# WIFI.net
KiCad netlist of a schematic drawn in Altium Designer
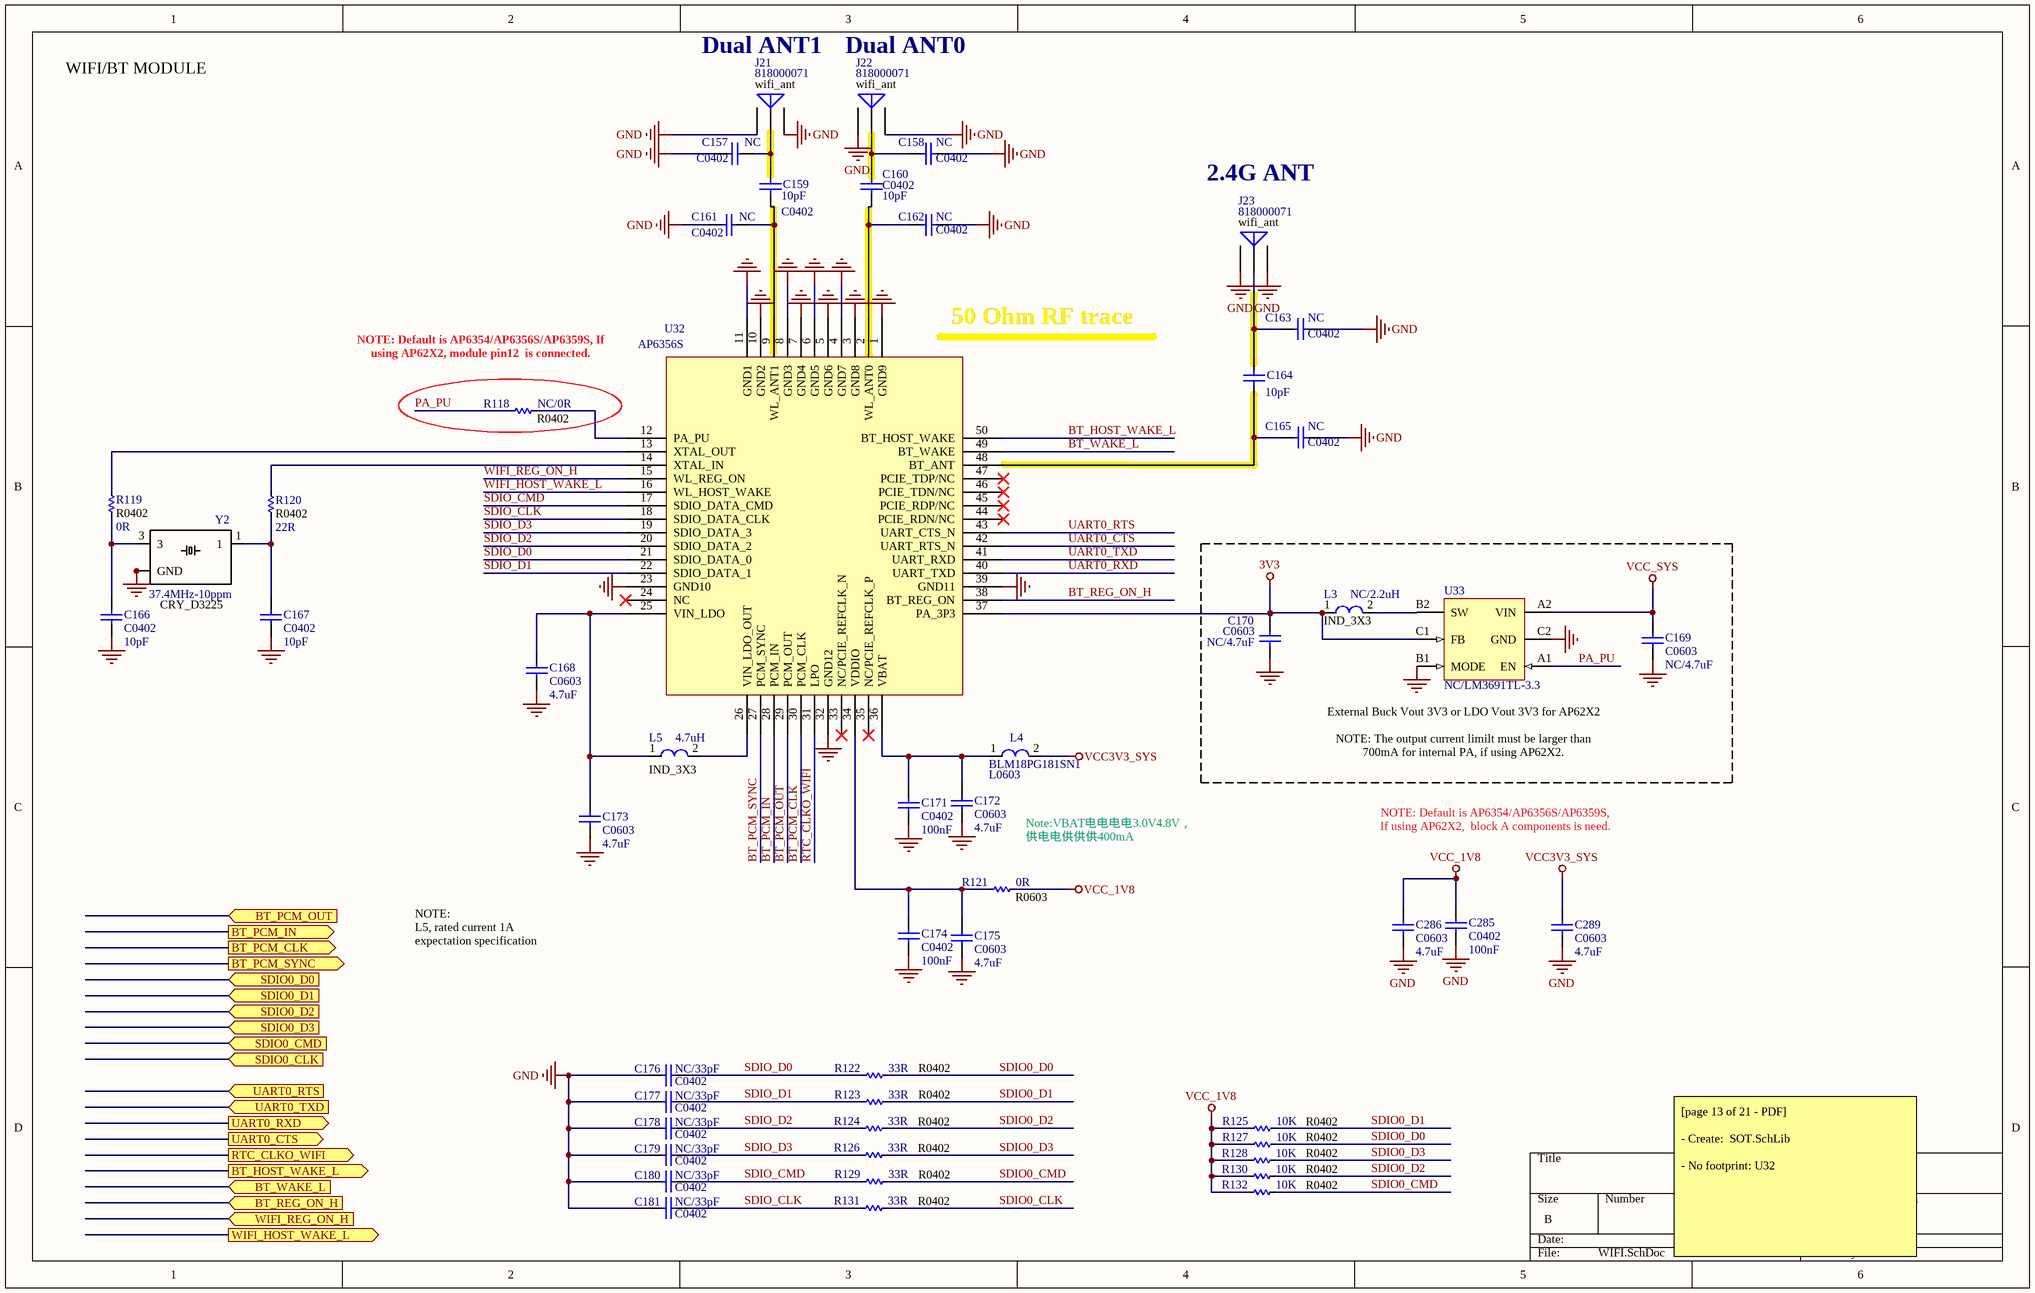
[diagram p0: WIFI.SchDoc]

(export (version "E")
  (design (tool "Eeschema 10.0.6"))
  (components
    (comp (ref "C157")
      (value "C0402")
      (footprint "C 0402")
      (description "Capacitor")
      (fields (field (name "ALTIUM_VALUE") "NC") (field (name "PUBLISHER") "Altium Limited"))
      (libsource (lib "Miscellaneous Devices") (part "Cap"))
    )
    (comp (ref "C158")
      (value "C0402")
      (footprint "C 0402")
      (description "Capacitor")
      (fields (field (name "ALTIUM_VALUE") "NC") (field (name "PUBLISHER") "Altium Limited"))
      (libsource (lib "Miscellaneous Devices") (part "Cap"))
    )
    (comp (ref "C159")
      (value "C0402")
      (footprint "C 0402")
      (description "Capacitor")
      (fields (field (name "ALTIUM_VALUE") "10pF") (field (name "PUBLISHER") "Altium Limited"))
      (libsource (lib "Miscellaneous Devices") (part "Cap"))
    )
    (comp (ref "C160")
      (value "C0402")
      (footprint "C 0402")
      (description "Capacitor")
      (fields (field (name "ALTIUM_VALUE") "10pF") (field (name "PUBLISHER") "Altium Limited"))
      (libsource (lib "Miscellaneous Devices") (part "Cap"))
    )
    (comp (ref "C161")
      (value "C0402")
      (footprint "C 0402")
      (description "Capacitor")
      (fields (field (name "ALTIUM_VALUE") "NC") (field (name "PUBLISHER") "Altium Limited"))
      (libsource (lib "Miscellaneous Devices") (part "Cap"))
    )
    (comp (ref "C162")
      (value "C0402")
      (footprint "C 0402")
      (description "Capacitor")
      (fields (field (name "ALTIUM_VALUE") "NC") (field (name "PUBLISHER") "Altium Limited"))
      (libsource (lib "Miscellaneous Devices") (part "Cap"))
    )
    (comp (ref "C163")
      (value "C0402")
      (footprint "C 0402")
      (description "Capacitor")
      (fields (field (name "ALTIUM_VALUE") "NC") (field (name "PUBLISHER") "Altium Limited"))
      (libsource (lib "Miscellaneous Devices") (part "Cap"))
    )
    (comp (ref "C164")
      (value "10pF")
      (footprint "C 0402")
      (description "Capacitor")
      (fields (field (name "Comment") "C0402") (field (name "PUBLISHER") "Altium Limited"))
      (libsource (lib "Miscellaneous Devices") (part "Cap"))
    )
    (comp (ref "C165")
      (value "C0402")
      (footprint "C 0402")
      (description "Capacitor")
      (fields (field (name "ALTIUM_VALUE") "NC") (field (name "PUBLISHER") "Altium Limited"))
      (libsource (lib "Miscellaneous Devices") (part "Cap"))
    )
    (comp (ref "C166")
      (value "C0402")
      (footprint "C 0402")
      (description "Capacitor")
      (fields (field (name "ALTIUM_VALUE") "10pF") (field (name "PUBLISHER") "Altium Limited"))
      (libsource (lib "Miscellaneous Devices") (part "Cap"))
    )
    (comp (ref "C167")
      (value "C0402")
      (footprint "C 0402")
      (description "Capacitor")
      (fields (field (name "ALTIUM_VALUE") "10pF") (field (name "PUBLISHER") "Altium Limited"))
      (libsource (lib "Miscellaneous Devices") (part "Cap"))
    )
    (comp (ref "C168")
      (value "C0603")
      (footprint "C 0603")
      (description "Capacitor")
      (fields (field (name "ALTIUM_VALUE") "4.7uF") (field (name "PUBLISHER") "Altium Limited"))
      (libsource (lib "Miscellaneous Devices") (part "Cap"))
    )
    (comp (ref "C169")
      (value "C0603")
      (footprint "C 0603")
      (description "Capacitor")
      (fields (field (name "ALTIUM_VALUE") "NC/4.7uF") (field (name "PUBLISHER") "Altium Limited"))
      (libsource (lib "Miscellaneous Devices") (part "Cap"))
    )
    (comp (ref "C170")
      (value "C0603")
      (footprint "C 0603")
      (description "Capacitor")
      (fields (field (name "ALTIUM_VALUE") "NC/4.7uF") (field (name "PUBLISHER") "Altium Limited"))
      (libsource (lib "Miscellaneous Devices") (part "Cap"))
    )
    (comp (ref "C171")
      (value "C0402")
      (footprint "C 0402")
      (description "Capacitor")
      (fields (field (name "ALTIUM_VALUE") "100nF") (field (name "PUBLISHER") "Altium Limited"))
      (libsource (lib "Miscellaneous Devices") (part "Cap"))
    )
    (comp (ref "C172")
      (value "C0603")
      (footprint "C 0603")
      (description "Capacitor")
      (fields (field (name "ALTIUM_VALUE") "4.7uF") (field (name "PUBLISHER") "Altium Limited"))
      (libsource (lib "Miscellaneous Devices") (part "Cap"))
    )
    (comp (ref "C173")
      (value "C0603")
      (footprint "C 0603")
      (description "Capacitor")
      (fields (field (name "ALTIUM_VALUE") "4.7uF") (field (name "PUBLISHER") "Altium Limited"))
      (libsource (lib "Miscellaneous Devices") (part "Cap"))
    )
    (comp (ref "C174")
      (value "C0402")
      (footprint "C 0402")
      (description "Capacitor")
      (fields (field (name "ALTIUM_VALUE") "100nF") (field (name "PUBLISHER") "Altium Limited"))
      (libsource (lib "Miscellaneous Devices") (part "Cap"))
    )
    (comp (ref "C175")
      (value "C0603")
      (footprint "C 0603")
      (description "Capacitor")
      (fields (field (name "ALTIUM_VALUE") "4.7uF") (field (name "PUBLISHER") "Altium Limited"))
      (libsource (lib "Miscellaneous Devices") (part "Cap"))
    )
    (comp (ref "C176")
      (value "C0402")
      (footprint "C 0402")
      (description "Capacitor")
      (fields (field (name "ALTIUM_VALUE") "NC/33pF") (field (name "PUBLISHER") "Altium Limited"))
      (libsource (lib "Miscellaneous Devices") (part "Cap"))
    )
    (comp (ref "C177")
      (value "C0402")
      (footprint "C 0402")
      (description "Capacitor")
      (fields (field (name "ALTIUM_VALUE") "NC/33pF") (field (name "PUBLISHER") "Altium Limited"))
      (libsource (lib "Miscellaneous Devices") (part "Cap"))
    )
    (comp (ref "C178")
      (value "C0402")
      (footprint "C 0402")
      (description "Capacitor")
      (fields (field (name "ALTIUM_VALUE") "NC/33pF") (field (name "PUBLISHER") "Altium Limited"))
      (libsource (lib "Miscellaneous Devices") (part "Cap"))
    )
    (comp (ref "C179")
      (value "C0402")
      (footprint "C 0402")
      (description "Capacitor")
      (fields (field (name "ALTIUM_VALUE") "NC/33pF") (field (name "PUBLISHER") "Altium Limited"))
      (libsource (lib "Miscellaneous Devices") (part "Cap"))
    )
    (comp (ref "C180")
      (value "C0402")
      (footprint "C 0402")
      (description "Capacitor")
      (fields (field (name "ALTIUM_VALUE") "NC/33pF") (field (name "PUBLISHER") "Altium Limited"))
      (libsource (lib "Miscellaneous Devices") (part "Cap"))
    )
    (comp (ref "C181")
      (value "C0402")
      (footprint "C 0402")
      (description "Capacitor")
      (fields (field (name "ALTIUM_VALUE") "NC/33pF") (field (name "PUBLISHER") "Altium Limited"))
      (libsource (lib "Miscellaneous Devices") (part "Cap"))
    )
    (comp (ref "C285")
      (value "C0402")
      (footprint "C 0402")
      (description "Capacitor")
      (fields (field (name "ALTIUM_VALUE") "100nF") (field (name "PUBLISHER") "Altium Limited"))
      (libsource (lib "Miscellaneous Devices") (part "Cap"))
    )
    (comp (ref "C286")
      (value "C0603")
      (footprint "C 0603")
      (description "Capacitor")
      (fields (field (name "ALTIUM_VALUE") "4.7uF") (field (name "PUBLISHER") "Altium Limited"))
      (libsource (lib "Miscellaneous Devices") (part "Cap"))
    )
    (comp (ref "C289")
      (value "C0603")
      (footprint "C 0603")
      (description "Capacitor")
      (fields (field (name "ALTIUM_VALUE") "4.7uF") (field (name "PUBLISHER") "Altium Limited"))
      (libsource (lib "Miscellaneous Devices") (part "Cap"))
    )
    (comp (ref "J21")
      (value "818000071")
      (footprint "CONN/IPX/SMD")
      (description "Generic Antenna")
      (fields (field (name "ALTIUM_UNNAMED_1") "wifi_ant") (field (name "PUBLISHER") "Altium Limited"))
      (libsource (lib "SOT") (part "Antenna"))
    )
    (comp (ref "J22")
      (value "818000071")
      (footprint "CONN/IPX/SMD")
      (description "Generic Antenna")
      (fields (field (name "ALTIUM_UNNAMED_1") "wifi_ant") (field (name "PUBLISHER") "Altium Limited"))
      (libsource (lib "SOT") (part "Antenna"))
    )
    (comp (ref "J23")
      (value "818000071")
      (footprint "CONN/IPX/SMD")
      (description "Generic Antenna")
      (fields (field (name "ALTIUM_UNNAMED_1") "wifi_ant") (field (name "PUBLISHER") "Altium Limited"))
      (libsource (lib "SOT") (part "Antenna"))
    )
    (comp (ref "L3")
      (value "NC/2.2uH")
      (footprint "L-SMD-M-7.3x4.5")
      (fields
        (field (name "PARTNO") "78477010")
        (field (name "MANUFACTURER") "Wurth Elektronik")
        (field (name "ALTIUM_UNNAMED_1") "IND_3X3")
        (field (name "CREATED BY") "Baojun Chen")
      )
      (libsource (lib "LIBRARY") (part "L-SMD-1"))
    )
    (comp (ref "L4")
      (value "L0603")
      (footprint "L-SMD-M-12x10")
      (fields
        (field (name "PARTNO") "78477010")
        (field (name "MANUFACTURER") "Wurth Elektronik")
        (field (name "ALTIUM_UNNAMED_1") "BLM18PG181SN1")
        (field (name "CREATED BY") "Baojun Chen")
      )
      (libsource (lib "LIBRARY") (part "L-SMD-1"))
    )
    (comp (ref "L5")
      (value "4.7uH")
      (footprint "L-SMD-M-7.3x4.5")
      (fields
        (field (name "PARTNO") "78477010")
        (field (name "MANUFACTURER") "Wurth Elektronik")
        (field (name "ALTIUM_UNNAMED_1") "IND_3X3")
        (field (name "CREATED BY") "Baojun Chen")
      )
      (libsource (lib "LIBRARY") (part "L-SMD-1"))
    )
    (comp (ref "R118")
      (value "R0402")
      (footprint "R 0402")
      (description "Resistor")
      (fields
        (field (name "MANUFACTURER") "Generic Components")
        (field (name "ALTIUM_VALUE") "NC/0R")
        (field (name "PUBLISHER") "Altium Hobart Technology Centre")
      )
      (libsource (lib "LIBRARY") (part "Res-SMD"))
    )
    (comp (ref "R119")
      (value "R0402")
      (footprint "R 0402")
      (description "Resistor")
      (fields
        (field (name "MANUFACTURER") "Generic Components")
        (field (name "ALTIUM_VALUE") "0R")
        (field (name "PUBLISHER") "Altium Hobart Technology Centre")
      )
      (libsource (lib "LIBRARY") (part "Res-SMD"))
    )
    (comp (ref "R120")
      (value "R0402")
      (footprint "R 0402")
      (description "Resistor")
      (fields
        (field (name "MANUFACTURER") "Generic Components")
        (field (name "ALTIUM_VALUE") "22R")
        (field (name "PUBLISHER") "Altium Hobart Technology Centre")
      )
      (libsource (lib "LIBRARY") (part "Res-SMD"))
    )
    (comp (ref "R121")
      (value "R0603")
      (footprint "R 0603")
      (description "Resistor")
      (fields
        (field (name "MANUFACTURER") "Generic Components")
        (field (name "ALTIUM_VALUE") "0R")
        (field (name "PUBLISHER") "Altium Hobart Technology Centre")
      )
      (libsource (lib "LIBRARY") (part "Res-SMD"))
    )
    (comp (ref "R122")
      (value "R0402")
      (footprint "R 0402")
      (description "Resistor")
      (fields
        (field (name "MANUFACTURER") "Generic Components")
        (field (name "ALTIUM_VALUE") "33R")
        (field (name "PUBLISHER") "Altium Hobart Technology Centre")
      )
      (libsource (lib "LIBRARY") (part "Res-SMD"))
    )
    (comp (ref "R123")
      (value "R0402")
      (footprint "R 0402")
      (description "Resistor")
      (fields
        (field (name "MANUFACTURER") "Generic Components")
        (field (name "ALTIUM_VALUE") "33R")
        (field (name "PUBLISHER") "Altium Hobart Technology Centre")
      )
      (libsource (lib "LIBRARY") (part "Res-SMD"))
    )
    (comp (ref "R124")
      (value "R0402")
      (footprint "R 0402")
      (description "Resistor")
      (fields
        (field (name "MANUFACTURER") "Generic Components")
        (field (name "ALTIUM_VALUE") "33R")
        (field (name "PUBLISHER") "Altium Hobart Technology Centre")
      )
      (libsource (lib "LIBRARY") (part "Res-SMD"))
    )
    (comp (ref "R125")
      (value "R0402")
      (footprint "R 0402")
      (description "Resistor")
      (fields
        (field (name "MANUFACTURER") "Generic Components")
        (field (name "ALTIUM_VALUE") "10K")
        (field (name "PUBLISHER") "Altium Hobart Technology Centre")
      )
      (libsource (lib "LIBRARY") (part "Res-SMD"))
    )
    (comp (ref "R126")
      (value "R0402")
      (footprint "R 0402")
      (description "Resistor")
      (fields
        (field (name "MANUFACTURER") "Generic Components")
        (field (name "ALTIUM_VALUE") "33R")
        (field (name "PUBLISHER") "Altium Hobart Technology Centre")
      )
      (libsource (lib "LIBRARY") (part "Res-SMD"))
    )
    (comp (ref "R127")
      (value "R0402")
      (footprint "R 0402")
      (description "Resistor")
      (fields
        (field (name "MANUFACTURER") "Generic Components")
        (field (name "ALTIUM_VALUE") "10K")
        (field (name "PUBLISHER") "Altium Hobart Technology Centre")
      )
      (libsource (lib "LIBRARY") (part "Res-SMD"))
    )
    (comp (ref "R128")
      (value "R0402")
      (footprint "R 0402")
      (description "Resistor")
      (fields
        (field (name "MANUFACTURER") "Generic Components")
        (field (name "ALTIUM_VALUE") "10K")
        (field (name "PUBLISHER") "Altium Hobart Technology Centre")
      )
      (libsource (lib "LIBRARY") (part "Res-SMD"))
    )
    (comp (ref "R129")
      (value "R0402")
      (footprint "R 0402")
      (description "Resistor")
      (fields
        (field (name "MANUFACTURER") "Generic Components")
        (field (name "ALTIUM_VALUE") "33R")
        (field (name "PUBLISHER") "Altium Hobart Technology Centre")
      )
      (libsource (lib "LIBRARY") (part "Res-SMD"))
    )
    (comp (ref "R130")
      (value "R0402")
      (footprint "R 0402")
      (description "Resistor")
      (fields
        (field (name "MANUFACTURER") "Generic Components")
        (field (name "ALTIUM_VALUE") "10K")
        (field (name "PUBLISHER") "Altium Hobart Technology Centre")
      )
      (libsource (lib "LIBRARY") (part "Res-SMD"))
    )
    (comp (ref "R131")
      (value "R0402")
      (footprint "R 0402")
      (description "Resistor")
      (fields
        (field (name "MANUFACTURER") "Generic Components")
        (field (name "ALTIUM_VALUE") "33R")
        (field (name "PUBLISHER") "Altium Hobart Technology Centre")
      )
      (libsource (lib "LIBRARY") (part "Res-SMD"))
    )
    (comp (ref "R132")
      (value "R0402")
      (footprint "R 0402")
      (description "Resistor")
      (fields
        (field (name "MANUFACTURER") "Generic Components")
        (field (name "ALTIUM_VALUE") "10K")
        (field (name "PUBLISHER") "Altium Hobart Technology Centre")
      )
      (libsource (lib "LIBRARY") (part "Res-SMD"))
    )
    (comp (ref "U32") (value "AP6356S") (footprint "AP6356S") (libsource (lib "SOT") (part "AP6356S")))
    (comp (ref "U33")
      (value "NC/LM3691TL-3.3")
      (footprint "TLA06LCA")
      (fields
        (field (name "PARTNUMBER") "LM3691TL-3.3/NOPB")
        (field (name "MANUFACTURER") "National Semiconductor")
      )
      (libsource (lib "National Semiconductor MiscPower") (part "LM3691TL-3.3/NOPB"))
    )
    (comp (ref "Y2")
      (value "37.4MHz-10ppm")
      (footprint "Crystal 4-SMD 32x25")
      (description "Ultra Miniature Crystal, SMD Ceramic, 30.000MHZ, 10pF, 10ppm@25C, 10ppm -10+60C,")
      (fields
        (field (name "MF") "Abracon")
        (field (name "MP") "ABM8-30.000MHZ-10-1-U-T")
        (field (name "ALTIUM_UNNAMED_1") "CRY_D3225")
      )
      (libsource (lib "ABM8-30.000MHZ-10-1-U-T") (part "ABM8-30.000MHZ-10-1-U-T"))
    )
  )
  (nets
    (net (code "1") (name "/BT_HOST_WAKE_L") (class "Default")
      (node (ref "U32") (pin "50") (pinfunction "BT_HOST_WAKE_50") (pintype "passive"))
    )
    (net (code "2") (name "/BT_PCM_CLK") (class "Default")
      (node (ref "U32") (pin "30") (pinfunction "PCM_CLK_30") (pintype "passive"))
    )
    (net (code "3") (name "/BT_PCM_IN") (class "Default")
      (node (ref "U32") (pin "28") (pinfunction "PCM_IN_28") (pintype "passive"))
    )
    (net (code "4") (name "/BT_PCM_OUT") (class "Default")
      (node (ref "U32") (pin "29") (pinfunction "PCM_OUT_29") (pintype "passive"))
    )
    (net (code "5") (name "/BT_PCM_SYNC") (class "Default")
      (node (ref "U32") (pin "27") (pinfunction "PCM_SYNC_27") (pintype "passive"))
    )
    (net (code "6") (name "/BT_REG_ON_H") (class "Default")
      (node (ref "U32") (pin "38") (pinfunction "BT_REG_ON_38") (pintype "passive"))
    )
    (net (code "7") (name "/BT_WAKE_L") (class "Default")
      (node (ref "U32") (pin "49") (pinfunction "BT_WAKE_49") (pintype "passive"))
    )
    (net (code "8") (name "/PA_PU") (class "Default")
      (node (ref "R118") (pin "1") (pinfunction "1_1") (pintype "passive"))
      (node (ref "U33") (pin "A1") (pinfunction "EN_A1") (pintype "input"))
    )
    (net (code "9") (name "/RTC_CLKO_WIFI") (class "Default")
      (node (ref "U32") (pin "31") (pinfunction "LPO_31") (pintype "passive"))
    )
    (net (code "10") (name "/SDIO0_CLK") (class "Default")
      (node (ref "R131") (pin "2") (pinfunction "2_2") (pintype "passive"))
    )
    (net (code "11") (name "/SDIO0_CMD") (class "Default")
      (node (ref "R129") (pin "2") (pinfunction "2_2") (pintype "passive"))
      (node (ref "R132") (pin "2") (pinfunction "2_2") (pintype "passive"))
    )
    (net (code "12") (name "/SDIO0_D0") (class "Default")
      (node (ref "R122") (pin "2") (pinfunction "2_2") (pintype "passive"))
      (node (ref "R127") (pin "2") (pinfunction "2_2") (pintype "passive"))
    )
    (net (code "13") (name "/SDIO0_D1") (class "Default")
      (node (ref "R123") (pin "2") (pinfunction "2_2") (pintype "passive"))
      (node (ref "R125") (pin "2") (pinfunction "2_2") (pintype "passive"))
    )
    (net (code "14") (name "/SDIO0_D2") (class "Default")
      (node (ref "R124") (pin "2") (pinfunction "2_2") (pintype "passive"))
      (node (ref "R130") (pin "2") (pinfunction "2_2") (pintype "passive"))
    )
    (net (code "15") (name "/SDIO0_D3") (class "Default")
      (node (ref "R126") (pin "2") (pinfunction "2_2") (pintype "passive"))
      (node (ref "R128") (pin "2") (pinfunction "2_2") (pintype "passive"))
    )
    (net (code "16") (name "/SDIO_CLK") (class "Default")
      (node (ref "C181") (pin "2") (pinfunction "2_2") (pintype "passive"))
      (node (ref "R131") (pin "1") (pinfunction "1_1") (pintype "passive"))
      (node (ref "U32") (pin "18") (pinfunction "SDIO_DATA_CLK_18") (pintype "passive"))
    )
    (net (code "17") (name "/SDIO_CMD") (class "Default")
      (node (ref "C180") (pin "2") (pinfunction "2_2") (pintype "passive"))
      (node (ref "R129") (pin "1") (pinfunction "1_1") (pintype "passive"))
      (node (ref "U32") (pin "17") (pinfunction "SDIO_DATA_CMD_17") (pintype "passive"))
    )
    (net (code "18") (name "/SDIO_D0") (class "Default")
      (node (ref "C176") (pin "2") (pinfunction "2_2") (pintype "passive"))
      (node (ref "R122") (pin "1") (pinfunction "1_1") (pintype "passive"))
      (node (ref "U32") (pin "21") (pinfunction "SDIO_DATA_0_21") (pintype "passive"))
    )
    (net (code "19") (name "/SDIO_D1") (class "Default")
      (node (ref "C177") (pin "2") (pinfunction "2_2") (pintype "passive"))
      (node (ref "R123") (pin "1") (pinfunction "1_1") (pintype "passive"))
      (node (ref "U32") (pin "22") (pinfunction "SDIO_DATA_1_22") (pintype "passive"))
    )
    (net (code "20") (name "/SDIO_D2") (class "Default")
      (node (ref "C178") (pin "2") (pinfunction "2_2") (pintype "passive"))
      (node (ref "R124") (pin "1") (pinfunction "1_1") (pintype "passive"))
      (node (ref "U32") (pin "20") (pinfunction "SDIO_DATA_2_20") (pintype "passive"))
    )
    (net (code "21") (name "/SDIO_D3") (class "Default")
      (node (ref "C179") (pin "2") (pinfunction "2_2") (pintype "passive"))
      (node (ref "R126") (pin "1") (pinfunction "1_1") (pintype "passive"))
      (node (ref "U32") (pin "19") (pinfunction "SDIO_DATA_3_19") (pintype "passive"))
    )
    (net (code "22") (name "/UART0_CTS") (class "Default")
      (node (ref "U32") (pin "42") (pinfunction "UART_RTS_N_42") (pintype "passive"))
    )
    (net (code "23") (name "/UART0_RTS") (class "Default")
      (node (ref "U32") (pin "43") (pinfunction "UART_CTS_N_43") (pintype "passive"))
    )
    (net (code "24") (name "/UART0_RXD") (class "Default")
      (node (ref "U32") (pin "40") (pinfunction "UART_TXD_40") (pintype "passive"))
    )
    (net (code "25") (name "/UART0_TXD") (class "Default")
      (node (ref "U32") (pin "41") (pinfunction "UART_RXD_41") (pintype "passive"))
    )
    (net (code "26") (name "/WIFI_HOST_WAKE_L") (class "Default")
      (node (ref "U32") (pin "16") (pinfunction "WL_HOST_WAKE_16") (pintype "passive"))
    )
    (net (code "27") (name "/WIFI_REG_ON_H") (class "Default")
      (node (ref "U32") (pin "15") (pinfunction "WL_REG_ON_15") (pintype "passive"))
    )
    (net (code "28") (name "3V3") (class "Default")
      (node (ref "C170") (pin "2") (pinfunction "2_2") (pintype "passive"))
      (node (ref "L3") (pin "1") (pinfunction "1_1") (pintype "passive"))
      (node (ref "U32") (pin "37") (pinfunction "PA_3P3_37") (pintype "passive"))
      (node (ref "U33") (pin "C1") (pinfunction "FB_C1") (pintype "input"))
    )
    (net (code "29") (name "GND") (class "Default")
      (node (ref "C157") (pin "2") (pinfunction "2_2") (pintype "passive"))
      (node (ref "C158") (pin "2") (pinfunction "2_2") (pintype "passive"))
      (node (ref "C161") (pin "2") (pinfunction "2_2") (pintype "passive"))
      (node (ref "C162") (pin "2") (pinfunction "2_2") (pintype "passive"))
      (node (ref "C163") (pin "2") (pinfunction "2_2") (pintype "passive"))
      (node (ref "C165") (pin "2") (pinfunction "2_2") (pintype "passive"))
      (node (ref "C166") (pin "1") (pinfunction "1_1") (pintype "passive"))
      (node (ref "C167") (pin "1") (pinfunction "1_1") (pintype "passive"))
      (node (ref "C168") (pin "1") (pinfunction "1_1") (pintype "passive"))
      (node (ref "C169") (pin "1") (pinfunction "1_1") (pintype "passive"))
      (node (ref "C170") (pin "1") (pinfunction "1_1") (pintype "passive"))
      (node (ref "C171") (pin "1") (pinfunction "1_1") (pintype "passive"))
      (node (ref "C172") (pin "1") (pinfunction "1_1") (pintype "passive"))
      (node (ref "C173") (pin "1") (pinfunction "1_1") (pintype "passive"))
      (node (ref "C174") (pin "1") (pinfunction "1_1") (pintype "passive"))
      (node (ref "C175") (pin "1") (pinfunction "1_1") (pintype "passive"))
      (node (ref "C176") (pin "1") (pinfunction "1_1") (pintype "passive"))
      (node (ref "C177") (pin "1") (pinfunction "1_1") (pintype "passive"))
      (node (ref "C178") (pin "1") (pinfunction "1_1") (pintype "passive"))
      (node (ref "C179") (pin "1") (pinfunction "1_1") (pintype "passive"))
      (node (ref "C180") (pin "1") (pinfunction "1_1") (pintype "passive"))
      (node (ref "C181") (pin "1") (pinfunction "1_1") (pintype "passive"))
      (node (ref "C285") (pin "1") (pinfunction "1_1") (pintype "passive"))
      (node (ref "C286") (pin "1") (pinfunction "1_1") (pintype "passive"))
      (node (ref "C289") (pin "1") (pinfunction "1_1") (pintype "passive"))
      (node (ref "J21") (pin "2") (pinfunction "2_2") (pintype "passive"))
      (node (ref "J21") (pin "3") (pinfunction "3_3") (pintype "passive"))
      (node (ref "J22") (pin "2") (pinfunction "2_2") (pintype "passive"))
      (node (ref "J22") (pin "3") (pinfunction "3_3") (pintype "passive"))
      (node (ref "J23") (pin "2") (pinfunction "2_2") (pintype "passive"))
      (node (ref "J23") (pin "3") (pinfunction "3_3") (pintype "passive"))
      (node (ref "U32") (pin "1") (pinfunction "GND9_1") (pintype "passive"))
      (node (ref "U32") (pin "10") (pinfunction "GND2_10") (pintype "passive"))
      (node (ref "U32") (pin "11") (pinfunction "GND1_11") (pintype "passive"))
      (node (ref "U32") (pin "23") (pinfunction "GND10_23") (pintype "passive"))
      (node (ref "U32") (pin "3") (pinfunction "GND8_3") (pintype "passive"))
      (node (ref "U32") (pin "32") (pinfunction "GND12_32") (pintype "passive"))
      (node (ref "U32") (pin "39") (pinfunction "GND11_39") (pintype "passive"))
      (node (ref "U32") (pin "4") (pinfunction "GND7_4") (pintype "passive"))
      (node (ref "U32") (pin "5") (pinfunction "GND6_5") (pintype "passive"))
      (node (ref "U32") (pin "6") (pinfunction "GND5_6") (pintype "passive"))
      (node (ref "U32") (pin "7") (pinfunction "GND4_7") (pintype "passive"))
      (node (ref "U32") (pin "8") (pinfunction "GND3_8") (pintype "passive"))
      (node (ref "U33") (pin "B1") (pinfunction "MODE_B1") (pintype "input"))
      (node (ref "U33") (pin "C2") (pinfunction "GND_C2") (pintype "power_in"))
      (node (ref "Y2") (pin "2") (pinfunction "GND_2") (pintype "power_in"))
      (node (ref "Y2") (pin "4") (pinfunction "GND_4") (pintype "power_in"))
    )
    (net (code "30") (name "Net-(C166-Pad2)") (class "Default")
      (node (ref "C166") (pin "2") (pinfunction "2_2") (pintype "passive"))
      (node (ref "R119") (pin "1") (pinfunction "1_1") (pintype "passive"))
      (node (ref "Y2") (pin "3") (pinfunction "3_3") (pintype "passive"))
    )
    (net (code "31") (name "Net-(C167-Pad2)") (class "Default")
      (node (ref "C167") (pin "2") (pinfunction "2_2") (pintype "passive"))
      (node (ref "R120") (pin "1") (pinfunction "1_1") (pintype "passive"))
      (node (ref "Y2") (pin "1") (pinfunction "1_1") (pintype "passive"))
    )
    (net (code "32") (name "Net-(J21-A)") (class "Default")
      (node (ref "C157") (pin "1") (pinfunction "1_1") (pintype "passive"))
      (node (ref "C159") (pin "1") (pinfunction "1_1") (pintype "passive"))
      (node (ref "J21") (pin "1") (pinfunction "A_1") (pintype "passive"))
    )
    (net (code "33") (name "Net-(J22-A)") (class "Default")
      (node (ref "C158") (pin "1") (pinfunction "1_1") (pintype "passive"))
      (node (ref "C160") (pin "1") (pinfunction "1_1") (pintype "passive"))
      (node (ref "J22") (pin "1") (pinfunction "A_1") (pintype "passive"))
    )
    (net (code "34") (name "Net-(J23-A)") (class "Default")
      (node (ref "C163") (pin "1") (pinfunction "1_1") (pintype "passive"))
      (node (ref "C164") (pin "1") (pinfunction "1_1") (pintype "passive"))
      (node (ref "J23") (pin "1") (pinfunction "A_1") (pintype "passive"))
    )
    (net (code "35") (name "Net-(U32-BT_ANT)") (class "Default")
      (node (ref "C164") (pin "2") (pinfunction "2_2") (pintype "passive"))
      (node (ref "C165") (pin "1") (pinfunction "1_1") (pintype "passive"))
      (node (ref "U32") (pin "48") (pinfunction "BT_ANT_48") (pintype "passive"))
    )
    (net (code "36") (name "Net-(U32-PA_PU)") (class "Default")
      (node (ref "R118") (pin "2") (pinfunction "2_2") (pintype "passive"))
      (node (ref "U32") (pin "12") (pinfunction "PA_PU_12") (pintype "passive"))
    )
    (net (code "37") (name "Net-(U32-VBAT)") (class "Default")
      (node (ref "C171") (pin "2") (pinfunction "2_2") (pintype "passive"))
      (node (ref "C172") (pin "2") (pinfunction "2_2") (pintype "passive"))
      (node (ref "L4") (pin "1") (pinfunction "1_1") (pintype "passive"))
      (node (ref "U32") (pin "36") (pinfunction "VBAT_36") (pintype "passive"))
    )
    (net (code "38") (name "Net-(U32-VDDIO)") (class "Default")
      (node (ref "C174") (pin "2") (pinfunction "2_2") (pintype "passive"))
      (node (ref "C175") (pin "2") (pinfunction "2_2") (pintype "passive"))
      (node (ref "R121") (pin "1") (pinfunction "1_1") (pintype "passive"))
      (node (ref "U32") (pin "34") (pinfunction "VDDIO_34") (pintype "passive"))
    )
    (net (code "39") (name "Net-(U32-VIN_LDO)") (class "Default")
      (node (ref "C168") (pin "2") (pinfunction "2_2") (pintype "passive"))
      (node (ref "C173") (pin "2") (pinfunction "2_2") (pintype "passive"))
      (node (ref "L5") (pin "1") (pinfunction "1_1") (pintype "passive"))
      (node (ref "U32") (pin "25") (pinfunction "VIN_LDO_25") (pintype "passive"))
    )
    (net (code "40") (name "Net-(U32-VIN_LDO_OUT)") (class "Default")
      (node (ref "L5") (pin "2") (pinfunction "2_2") (pintype "passive"))
      (node (ref "U32") (pin "26") (pinfunction "VIN_LDO_OUT_26") (pintype "passive"))
    )
    (net (code "41") (name "Net-(U32-WL_ANT0)") (class "Default")
      (node (ref "C160") (pin "2") (pinfunction "2_2") (pintype "passive"))
      (node (ref "C162") (pin "1") (pinfunction "1_1") (pintype "passive"))
      (node (ref "U32") (pin "2") (pinfunction "WL_ANT0_2") (pintype "passive"))
    )
    (net (code "42") (name "Net-(U32-WL_ANT1)") (class "Default")
      (node (ref "C159") (pin "2") (pinfunction "2_2") (pintype "passive"))
      (node (ref "C161") (pin "1") (pinfunction "1_1") (pintype "passive"))
      (node (ref "U32") (pin "9") (pinfunction "WL_ANT1_9") (pintype "passive"))
    )
    (net (code "43") (name "Net-(U32-XTAL_IN)") (class "Default")
      (node (ref "R120") (pin "2") (pinfunction "2_2") (pintype "passive"))
      (node (ref "U32") (pin "14") (pinfunction "XTAL_IN_14") (pintype "passive"))
    )
    (net (code "44") (name "Net-(U32-XTAL_OUT)") (class "Default")
      (node (ref "R119") (pin "2") (pinfunction "2_2") (pintype "passive"))
      (node (ref "U32") (pin "13") (pinfunction "XTAL_OUT_13") (pintype "passive"))
    )
    (net (code "45") (name "Net-(U33-SW)") (class "Default")
      (node (ref "L3") (pin "2") (pinfunction "2_2") (pintype "passive"))
      (node (ref "U33") (pin "B2") (pinfunction "SW_B2") (pintype "power_in"))
    )
    (net (code "46") (name "VCC3V3_SYS") (class "Default")
      (node (ref "C289") (pin "2") (pinfunction "2_2") (pintype "passive"))
      (node (ref "L4") (pin "2") (pinfunction "2_2") (pintype "passive"))
    )
    (net (code "47") (name "VCC_1V8") (class "Default")
      (node (ref "C285") (pin "2") (pinfunction "2_2") (pintype "passive"))
      (node (ref "C286") (pin "2") (pinfunction "2_2") (pintype "passive"))
      (node (ref "R121") (pin "2") (pinfunction "2_2") (pintype "passive"))
      (node (ref "R125") (pin "1") (pinfunction "1_1") (pintype "passive"))
      (node (ref "R127") (pin "1") (pinfunction "1_1") (pintype "passive"))
      (node (ref "R128") (pin "1") (pinfunction "1_1") (pintype "passive"))
      (node (ref "R130") (pin "1") (pinfunction "1_1") (pintype "passive"))
      (node (ref "R132") (pin "1") (pinfunction "1_1") (pintype "passive"))
    )
    (net (code "48") (name "VCC_SYS") (class "Default")
      (node (ref "C169") (pin "2") (pinfunction "2_2") (pintype "passive"))
      (node (ref "U33") (pin "A2") (pinfunction "VIN_A2") (pintype "power_in"))
    )
    (net (code "49") (name "unconnected-(U32-NC-Pad24)") (class "Default")
      (node (ref "U32") (pin "24") (pinfunction "NC_24") (pintype "passive+no_connect"))
    )
    (net (code "50") (name "unconnected-(U32-NC{slash}PCIE_REFCLK_N-Pad33)") (class "Default")
      (node (ref "U32") (pin "33") (pinfunction "NC/PCIE_REFCLK_N_33") (pintype "passive+no_connect"))
    )
    (net (code "51") (name "unconnected-(U32-NC{slash}PCIE_REFCLK_P-Pad35)") (class "Default")
      (node (ref "U32") (pin "35") (pinfunction "NC/PCIE_REFCLK_P_35") (pintype "passive+no_connect"))
    )
    (net (code "52") (name "unconnected-(U32-PCIE_RDN{slash}NC-Pad44)") (class "Default")
      (node (ref "U32") (pin "44") (pinfunction "PCIE_RDN/NC_44") (pintype "passive+no_connect"))
    )
    (net (code "53") (name "unconnected-(U32-PCIE_RDP{slash}NC-Pad45)") (class "Default")
      (node (ref "U32") (pin "45") (pinfunction "PCIE_RDP/NC_45") (pintype "passive+no_connect"))
    )
    (net (code "54") (name "unconnected-(U32-PCIE_TDN{slash}NC-Pad46)") (class "Default")
      (node (ref "U32") (pin "46") (pinfunction "PCIE_TDN/NC_46") (pintype "passive+no_connect"))
    )
    (net (code "55") (name "unconnected-(U32-PCIE_TDP{slash}NC-Pad47)") (class "Default")
      (node (ref "U32") (pin "47") (pinfunction "PCIE_TDP/NC_47") (pintype "passive+no_connect"))
    )
  )
)
